# Sheet6.net
KiCad netlist of a schematic drawn in Altium Designer
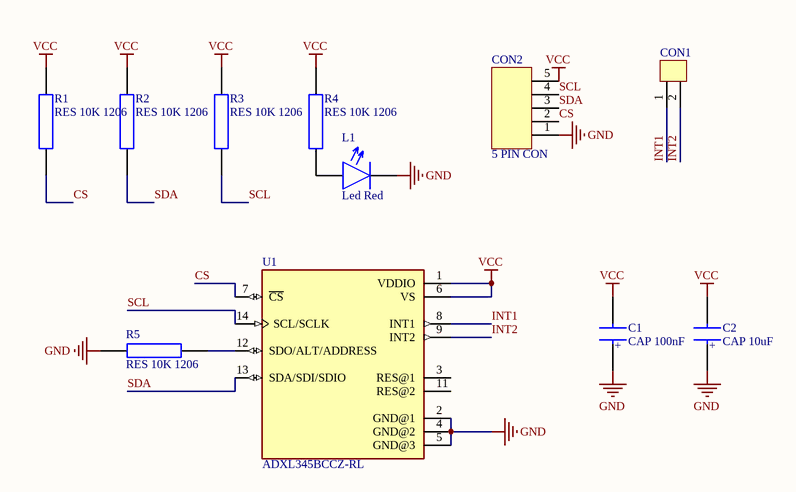
[diagram p0: Sheet6.SchDoc]

(export (version "E")
  (design (tool "Eeschema 10.0.6"))
  (components
    (comp (ref "C1")
      (value "CAP 100nF")
      (footprint "CAP_805")
      (description "0805 smd")
      (libsource (lib "Udemy_Schlib1") (part "CAP 1uF"))
    )
    (comp (ref "C2")
      (value "CAP 10uF")
      (footprint "CAP_805")
      (description "0805 smd")
      (libsource (lib "Udemy_Schlib1") (part "CAP 1uF"))
    )
    (comp (ref "CON1")
      (value "2 Pin Jst Konnektör")
      (footprint "2 pin konnektor")
      (description "2.50 mm 2 pin jst")
      (libsource (lib "Udemy_Schlib1") (part "2 Pin Jst Konnektör"))
    )
    (comp (ref "CON2")
      (value "5 PIN CON")
      (footprint "5 PIN 2.54MM")
      (description "2.54mm vertical connector")
      (libsource (lib "Udemy_Schlib1") (part "5 PIN CON"))
    )
    (comp (ref "L1")
      (value "Led Red")
      (footprint "Led 1206")
      (libsource (lib "Udemy_Schlib1") (part "Led Red"))
    )
    (comp (ref "R1")
      (value "RES 10K 1206")
      (footprint "RES_1206")
      (libsource (lib "Udemy_Schlib1") (part "RES 10K 1206"))
    )
    (comp (ref "R2")
      (value "RES 10K 1206")
      (footprint "RES_1206")
      (libsource (lib "Udemy_Schlib1") (part "RES 10K 1206"))
    )
    (comp (ref "R3")
      (value "RES 10K 1206")
      (footprint "RES_1206")
      (libsource (lib "Udemy_Schlib1") (part "RES 10K 1206"))
    )
    (comp (ref "R4")
      (value "RES 10K 1206")
      (footprint "RES_1206")
      (libsource (lib "Udemy_Schlib1") (part "RES 10K 1206"))
    )
    (comp (ref "R5")
      (value "RES 10K 1206")
      (footprint "RES_1206")
      (libsource (lib "Udemy_Schlib1") (part "RES 10K 1206"))
    )
    (comp (ref "U1")
      (value "ADXL345BCCZ-RL")
      (footprint "PQFN80P300X500X79-14N")
      (description "Accelerometer X, Y, Z Axis Â±2g, 4g, 8g, 16g 0.05Hz ~ 1.6kHz 14-LGA (3x5)")
      (fields (field (name "MF") "Analog Devices"))
      (libsource (lib "Schlib") (part "ADXL345BCCZ-RL"))
    )
  )
  (nets
    (net (code "1") (name "/CS") (class "Default")
      (node (ref "CON2") (pin "2") (pintype "passive"))
      (node (ref "R1") (pin "2") (pintype "passive"))
      (node (ref "U1") (pin "7") (pinfunction "~{CS}_7") (pintype "bidirectional"))
    )
    (net (code "2") (name "/INT1") (class "Default")
      (node (ref "CON1") (pin "1") (pintype "passive"))
      (node (ref "U1") (pin "8") (pinfunction "INT1_8") (pintype "output"))
    )
    (net (code "3") (name "/INT2") (class "Default")
      (node (ref "CON1") (pin "2") (pintype "passive"))
      (node (ref "U1") (pin "9") (pinfunction "INT2_9") (pintype "output"))
    )
    (net (code "4") (name "/SCL") (class "Default")
      (node (ref "CON2") (pin "4") (pintype "passive"))
      (node (ref "R3") (pin "2") (pintype "passive"))
      (node (ref "U1") (pin "14") (pinfunction "SCL/SCLK_14") (pintype "input"))
    )
    (net (code "5") (name "/SDA") (class "Default")
      (node (ref "CON2") (pin "3") (pintype "passive"))
      (node (ref "R2") (pin "2") (pintype "passive"))
      (node (ref "U1") (pin "13") (pinfunction "SDA/SDI/SDIO_13") (pintype "bidirectional"))
    )
    (net (code "6") (name "GND") (class "Default")
      (node (ref "C1") (pin "1") (pinfunction "1_1") (pintype "passive"))
      (node (ref "C2") (pin "1") (pinfunction "1_1") (pintype "passive"))
      (node (ref "CON2") (pin "1") (pintype "passive"))
      (node (ref "L1") (pin "2") (pintype "passive"))
      (node (ref "R5") (pin "1") (pintype "passive"))
      (node (ref "U1") (pin "2") (pinfunction "GND@1_2") (pintype "power_in"))
      (node (ref "U1") (pin "4") (pinfunction "GND@2_4") (pintype "power_in"))
      (node (ref "U1") (pin "5") (pinfunction "GND@3_5") (pintype "power_in"))
    )
    (net (code "7") (name "Net-(L1-Pad1)") (class "Default")
      (node (ref "L1") (pin "1") (pintype "passive"))
      (node (ref "R4") (pin "2") (pintype "passive"))
    )
    (net (code "8") (name "Net-(U1-SDO{slash}ALT{slash}ADDRESS)") (class "Default")
      (node (ref "R5") (pin "2") (pintype "passive"))
      (node (ref "U1") (pin "12") (pinfunction "SDO/ALT/ADDRESS_12") (pintype "bidirectional"))
    )
    (net (code "9") (name "VCC") (class "Default")
      (node (ref "C1") (pin "2") (pinfunction "2_2") (pintype "passive"))
      (node (ref "C2") (pin "2") (pinfunction "2_2") (pintype "passive"))
      (node (ref "CON2") (pin "5") (pintype "passive"))
      (node (ref "R1") (pin "1") (pintype "passive"))
      (node (ref "R2") (pin "1") (pintype "passive"))
      (node (ref "R3") (pin "1") (pintype "passive"))
      (node (ref "R4") (pin "1") (pintype "passive"))
      (node (ref "U1") (pin "1") (pinfunction "VDDIO_1") (pintype "power_in"))
      (node (ref "U1") (pin "6") (pinfunction "VS_6") (pintype "power_in"))
    )
    (net (code "10") (name "unconnected-(U1-RES@1-Pad3)") (class "Default")
      (node (ref "U1") (pin "3") (pinfunction "RES@1_3") (pintype "passive"))
    )
    (net (code "11") (name "unconnected-(U1-RES@2-Pad11)") (class "Default")
      (node (ref "U1") (pin "11") (pinfunction "RES@2_11") (pintype "passive"))
    )
  )
)
